# schematics.net
KiCad netlist of a schematic drawn in EAGLE
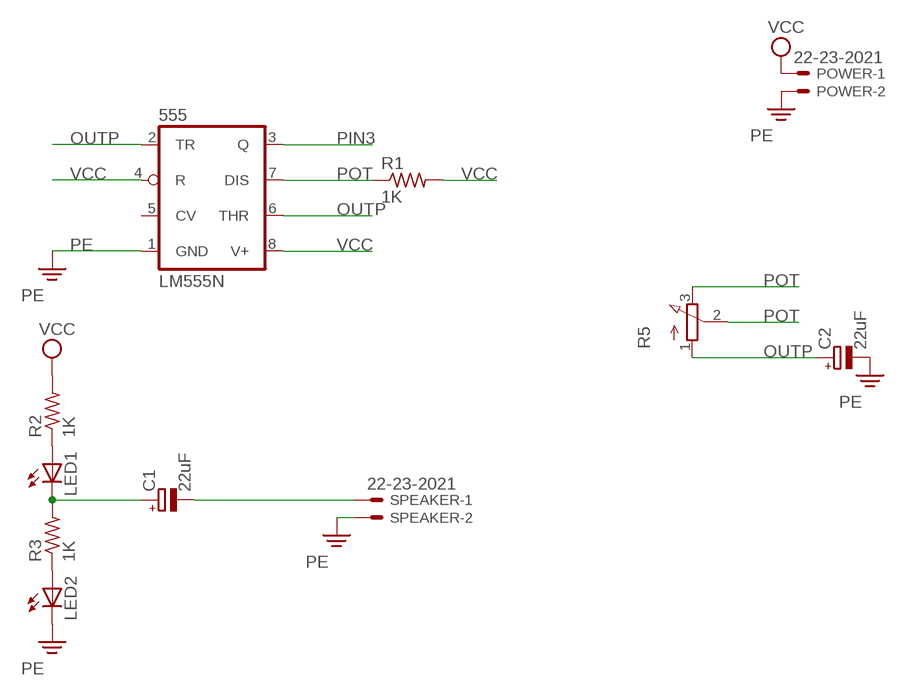
[diagram p0: schematic, sheet 1]

(export (version "E")
  (design (tool "Eeschema 10.0.6"))
  (components
    (comp (ref "555")
      (value "LM555N")
      (footprint "eagle-import:DIL08")
      (libsource (lib "eagle-import") (part "555NLM"))
    )
    (comp (ref "C1")
      (value "22uF")
      (footprint "eagle-import:E2,5-7")
      (libsource (lib "eagle-import") (part "CPOL-EUE2.5-7"))
    )
    (comp (ref "C2")
      (value "22uF")
      (footprint "eagle-import:E2,5-7")
      (libsource (lib "eagle-import") (part "CPOL-EUE2.5-7"))
    )
    (comp (ref "LED1")
      (value "LED5MM")
      (footprint "eagle-import:LED5MM")
      (libsource (lib "eagle-import") (part "LED5MM"))
    )
    (comp (ref "LED2")
      (value "LED5MM")
      (footprint "eagle-import:LED5MM")
      (libsource (lib "eagle-import") (part "LED5MM"))
    )
    (comp (ref "POWER")
      (value "22-23-2021")
      (footprint "eagle-import:22-23-2021")
      (fields (field (name "MF") "MOLEX"))
      (libsource (lib "eagle-import") (part "22-23-2021"))
    )
    (comp (ref "R1")
      (value "1K")
      (footprint "eagle-import:0207_10")
      (libsource (lib "eagle-import") (part "R-US_0207/10"))
    )
    (comp (ref "R2")
      (value "1K")
      (footprint "eagle-import:0207_10")
      (libsource (lib "eagle-import") (part "R-US_0207/10"))
    )
    (comp (ref "R3")
      (value "1K")
      (footprint "eagle-import:0207_10")
      (libsource (lib "eagle-import") (part "R-US_0207/10"))
    )
    (comp (ref "R5")
      (value "3RP/1610N")
      (footprint "eagle-import:3RP_1610N")
      (libsource (lib "eagle-import") (part "3RP/1610N"))
    )
    (comp (ref "SPEAKER")
      (value "22-23-2021")
      (footprint "eagle-import:22-23-2021")
      (fields (field (name "MF") "MOLEX"))
      (libsource (lib "eagle-import") (part "22-23-2021"))
    )
  )
  (nets
    (net (code "1") (name "/OUTP") (class "Default")
      (node (ref "555") (pin "2") (pinfunction "TR_2") (pintype "input"))
      (node (ref "555") (pin "6") (pinfunction "THR_6") (pintype "input"))
      (node (ref "C2") (pin "+") (pinfunction "+_+") (pintype "passive"))
      (node (ref "R5") (pin "1") (pinfunction "A_1") (pintype "passive"))
    )
    (net (code "2") (name "/PIN3") (class "Default")
      (node (ref "555") (pin "3") (pinfunction "Q_3") (pintype "output"))
      (node (ref "C1") (pin "+") (pinfunction "+_+") (pintype "passive"))
      (node (ref "LED1") (pin "K") (pinfunction "C_K") (pintype "passive"))
      (node (ref "R3") (pin "2") (pinfunction "2_2") (pintype "passive"))
    )
    (net (code "3") (name "/POT") (class "Default")
      (node (ref "555") (pin "7") (pinfunction "DIS_7") (pintype "input"))
      (node (ref "R1") (pin "1") (pinfunction "1_1") (pintype "passive"))
      (node (ref "R5") (pin "2") (pinfunction "S_2") (pintype "passive"))
      (node (ref "R5") (pin "3") (pinfunction "E_3") (pintype "passive"))
    )
    (net (code "4") (name "Net-(LED1-PadA)") (class "Default")
      (node (ref "LED1") (pin "A") (pinfunction "A_A") (pintype "passive"))
      (node (ref "R2") (pin "1") (pinfunction "1_1") (pintype "passive"))
    )
    (net (code "5") (name "Net-(LED2-PadA)") (class "Default")
      (node (ref "LED2") (pin "A") (pinfunction "A_A") (pintype "passive"))
      (node (ref "R3") (pin "1") (pinfunction "1_1") (pintype "passive"))
    )
    (net (code "6") (name "Net-(SPEAKERA-S)") (class "Default")
      (node (ref "C1") (pin "-") (pinfunction "-_-") (pintype "passive"))
      (node (ref "SPEAKER") (pin "1") (pinfunction "S_1") (pintype "passive"))
    )
    (net (code "7") (name "PE") (class "Default")
      (node (ref "555") (pin "1") (pinfunction "GND_1") (pintype "power_in"))
      (node (ref "C2") (pin "-") (pinfunction "-_-") (pintype "passive"))
      (node (ref "LED2") (pin "K") (pinfunction "C_K") (pintype "passive"))
      (node (ref "POWER") (pin "2") (pinfunction "S_2") (pintype "passive"))
      (node (ref "SPEAKER") (pin "2") (pinfunction "S_2") (pintype "passive"))
    )
    (net (code "8") (name "VCC") (class "Default")
      (node (ref "555") (pin "4") (pinfunction "R_4") (pintype "input"))
      (node (ref "555") (pin "8") (pinfunction "V+_8") (pintype "power_in"))
      (node (ref "POWER") (pin "1") (pinfunction "S_1") (pintype "passive"))
      (node (ref "R1") (pin "2") (pinfunction "2_2") (pintype "passive"))
      (node (ref "R2") (pin "2") (pinfunction "2_2") (pintype "passive"))
    )
    (net (code "9") (name "unconnected-(555-CV-Pad5)") (class "Default")
      (node (ref "555") (pin "5") (pinfunction "CV_5") (pintype "input"))
    )
  )
)
